# Ground_Station_Board.net
KiCad netlist of a schematic drawn in EAGLE
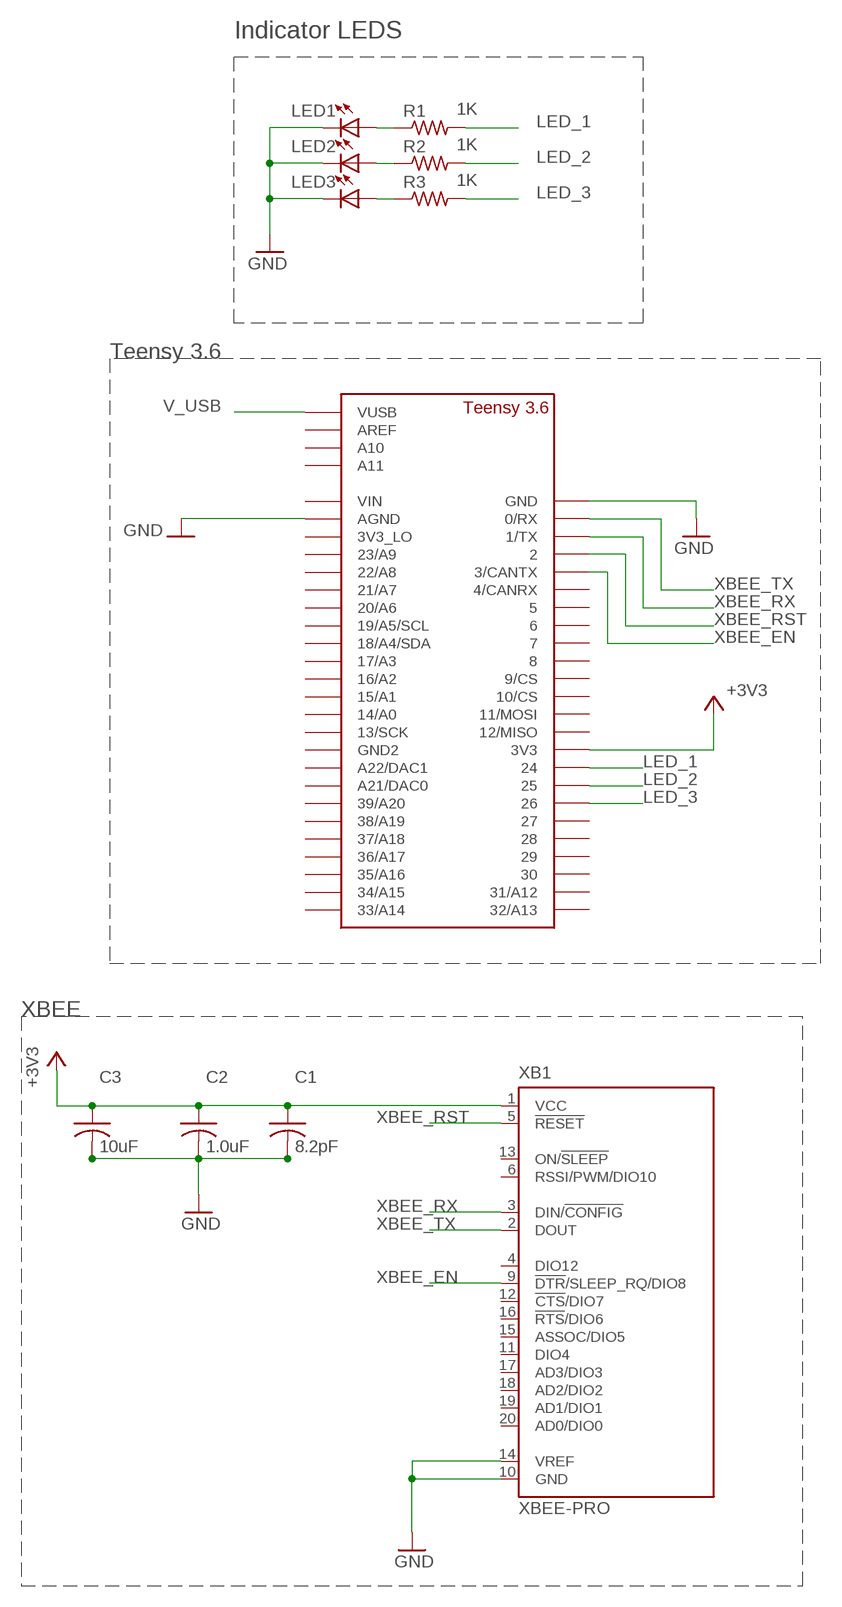
[diagram p0: schematic, sheet 1]

(export (version "E")
  (design (tool "Eeschema 10.0.6"))
  (components
    (comp (ref "C1")
      (value "8.2pF")
      (footprint "eagle-import:C025-024X044")
      (libsource (lib "eagle-import") (part "C-US025-024X044"))
    )
    (comp (ref "C2")
      (value "1.0uF")
      (footprint "eagle-import:C025-024X044")
      (libsource (lib "eagle-import") (part "C-US025-024X044"))
    )
    (comp (ref "C3")
      (value "10uF")
      (footprint "eagle-import:C025-024X044")
      (libsource (lib "eagle-import") (part "C-US025-024X044"))
    )
    (comp (ref "LED1")
      (value "LED5MM")
      (footprint "eagle-import:LED5MM")
      (libsource (lib "eagle-import") (part "LED5MM"))
    )
    (comp (ref "LED2")
      (value "LED5MM")
      (footprint "eagle-import:LED5MM")
      (libsource (lib "eagle-import") (part "LED5MM"))
    )
    (comp (ref "LED3")
      (value "LED5MM")
      (footprint "eagle-import:LED5MM")
      (libsource (lib "eagle-import") (part "LED5MM"))
    )
    (comp (ref "R1")
      (value "1K")
      (footprint "eagle-import:0207_7")
      (libsource (lib "eagle-import") (part "R-US_0207/7"))
    )
    (comp (ref "R2")
      (value "1K")
      (footprint "eagle-import:0207_7")
      (libsource (lib "eagle-import") (part "R-US_0207/7"))
    )
    (comp (ref "R3")
      (value "1K")
      (footprint "eagle-import:0207_7")
      (libsource (lib "eagle-import") (part "R-US_0207/7"))
    )
    (comp (ref "U$2")
      (value "TEENSY_3.5/3.6_BASIC")
      (footprint "eagle-import:TEENSY_3.5_3.6_BASIC")
      (libsource (lib "eagle-import") (part "TEENSY_3.5/3.6_BASIC"))
    )
    (comp (ref "XB1")
      (value "XBEE-PRO")
      (footprint "eagle-import:XBEE-PRO")
      (fields (field (name "MPN") "XBP24-AWI-001"))
      (libsource (lib "eagle-import") (part "XBEE-PRO"))
    )
  )
  (nets
    (net (code "1") (name "+3V3") (class "Default")
      (node (ref "C1") (pin "1") (pinfunction "1_1") (pintype "passive"))
      (node (ref "C2") (pin "1") (pinfunction "1_1") (pintype "passive"))
      (node (ref "C3") (pin "1") (pinfunction "1_1") (pintype "passive"))
      (node (ref "U$2") (pin "3V3") (pinfunction "3V3_3V3") (pintype "bidirectional"))
      (node (ref "XB1") (pin "1") (pinfunction "VCC_1") (pintype "power_in"))
    )
    (net (code "2") (name "/LED_1") (class "Default")
      (node (ref "R1") (pin "2") (pinfunction "2_2") (pintype "passive"))
      (node (ref "U$2") (pin "24") (pinfunction "24_24") (pintype "bidirectional"))
    )
    (net (code "3") (name "/LED_2") (class "Default")
      (node (ref "R2") (pin "2") (pinfunction "2_2") (pintype "passive"))
      (node (ref "U$2") (pin "25") (pinfunction "25_25") (pintype "bidirectional"))
    )
    (net (code "4") (name "/LED_3") (class "Default")
      (node (ref "R3") (pin "2") (pinfunction "2_2") (pintype "passive"))
      (node (ref "U$2") (pin "26") (pinfunction "26_26") (pintype "bidirectional"))
    )
    (net (code "5") (name "/V_USB") (class "Default")
      (node (ref "U$2") (pin "VUSB") (pinfunction "VUSB_VUSB") (pintype "bidirectional"))
    )
    (net (code "6") (name "/XBEE_EN") (class "Default")
      (node (ref "U$2") (pin "3/CANTX") (pinfunction "3/CANTX_3/CANTX") (pintype "bidirectional"))
      (node (ref "XB1") (pin "9") (pinfunction "~{DTR}/SLEEP_RQ/DIO8_9") (pintype "bidirectional"))
    )
    (net (code "7") (name "/XBEE_RST") (class "Default")
      (node (ref "U$2") (pin "2") (pinfunction "2_2") (pintype "bidirectional"))
      (node (ref "XB1") (pin "5") (pinfunction "~{RESET}_5") (pintype "input"))
    )
    (net (code "8") (name "/XBEE_RX") (class "Default")
      (node (ref "U$2") (pin "1/TX") (pinfunction "1/TX_1/TX") (pintype "bidirectional"))
      (node (ref "XB1") (pin "3") (pinfunction "DIN/~{CONFIG}_3") (pintype "input"))
    )
    (net (code "9") (name "/XBEE_TX") (class "Default")
      (node (ref "U$2") (pin "0/RX") (pinfunction "0/RX_0/RX") (pintype "bidirectional"))
      (node (ref "XB1") (pin "2") (pinfunction "DOUT_2") (pintype "output"))
    )
    (net (code "10") (name "GND") (class "Default")
      (node (ref "C1") (pin "2") (pinfunction "2_2") (pintype "passive"))
      (node (ref "C2") (pin "2") (pinfunction "2_2") (pintype "passive"))
      (node (ref "C3") (pin "2") (pinfunction "2_2") (pintype "passive"))
      (node (ref "LED1") (pin "K") (pinfunction "C_K") (pintype "passive"))
      (node (ref "LED2") (pin "K") (pinfunction "C_K") (pintype "passive"))
      (node (ref "LED3") (pin "K") (pinfunction "C_K") (pintype "passive"))
      (node (ref "U$2") (pin "AGND") (pinfunction "AGND_AGND") (pintype "bidirectional"))
      (node (ref "U$2") (pin "GND") (pinfunction "GND_GND") (pintype "bidirectional"))
      (node (ref "XB1") (pin "10") (pinfunction "GND_10") (pintype "power_in"))
      (node (ref "XB1") (pin "14") (pinfunction "VREF_14") (pintype "input"))
    )
    (net (code "11") (name "Net-(LED1-PadA)") (class "Default")
      (node (ref "LED1") (pin "A") (pinfunction "A_A") (pintype "passive"))
      (node (ref "R1") (pin "1") (pinfunction "1_1") (pintype "passive"))
    )
    (net (code "12") (name "Net-(LED2-PadA)") (class "Default")
      (node (ref "LED2") (pin "A") (pinfunction "A_A") (pintype "passive"))
      (node (ref "R2") (pin "1") (pinfunction "1_1") (pintype "passive"))
    )
    (net (code "13") (name "Net-(LED3-PadA)") (class "Default")
      (node (ref "LED3") (pin "A") (pinfunction "A_A") (pintype "passive"))
      (node (ref "R3") (pin "1") (pinfunction "1_1") (pintype "passive"))
    )
    (net (code "14") (name "unconnected-(U$2-A21{slash}DAC0-Pad21{slash}DAC0)") (class "Default")
      (node (ref "U$2") (pin "21/DAC0") (pinfunction "A21/DAC0_21/DAC0") (pintype "bidirectional"))
    )
    (net (code "15") (name "unconnected-(U$2-Pad3V3_LO)") (class "Default")
      (node (ref "U$2") (pin "3V3_LO") (pinfunction "3V3_LO_3V3_LO") (pintype "bidirectional"))
    )
    (net (code "16") (name "unconnected-(U$2-Pad4{slash}CANRX)") (class "Default")
      (node (ref "U$2") (pin "4/CANRX") (pinfunction "4/CANRX_4/CANRX") (pintype "bidirectional"))
    )
    (net (code "17") (name "unconnected-(U$2-Pad5)") (class "Default")
      (node (ref "U$2") (pin "5") (pinfunction "5_5") (pintype "bidirectional"))
    )
    (net (code "18") (name "unconnected-(U$2-Pad6)") (class "Default")
      (node (ref "U$2") (pin "6") (pinfunction "6_6") (pintype "bidirectional"))
    )
    (net (code "19") (name "unconnected-(U$2-Pad7)") (class "Default")
      (node (ref "U$2") (pin "7") (pinfunction "7_7") (pintype "bidirectional"))
    )
    (net (code "20") (name "unconnected-(U$2-Pad8)") (class "Default")
      (node (ref "U$2") (pin "8") (pinfunction "8_8") (pintype "bidirectional"))
    )
    (net (code "21") (name "unconnected-(U$2-Pad9{slash}CS)") (class "Default")
      (node (ref "U$2") (pin "9/CS") (pinfunction "9/CS_9/CS") (pintype "bidirectional"))
    )
    (net (code "22") (name "unconnected-(U$2-Pad10{slash}CS)") (class "Default")
      (node (ref "U$2") (pin "10/CS") (pinfunction "10/CS_10/CS") (pintype "bidirectional"))
    )
    (net (code "23") (name "unconnected-(U$2-Pad11{slash}MOSI)") (class "Default")
      (node (ref "U$2") (pin "11/MOSI") (pinfunction "11/MOSI_11/MOSI") (pintype "bidirectional"))
    )
    (net (code "24") (name "unconnected-(U$2-Pad12{slash}MISO)") (class "Default")
      (node (ref "U$2") (pin "12/MISO") (pinfunction "12/MISO_12/MISO") (pintype "bidirectional"))
    )
    (net (code "25") (name "unconnected-(U$2-Pad13{slash}SCK)") (class "Default")
      (node (ref "U$2") (pin "13/SCK") (pinfunction "13/SCK_13/SCK") (pintype "bidirectional"))
    )
    (net (code "26") (name "unconnected-(U$2-Pad14{slash}A0)") (class "Default")
      (node (ref "U$2") (pin "14/A0") (pinfunction "14/A0_14/A0") (pintype "bidirectional"))
    )
    (net (code "27") (name "unconnected-(U$2-Pad15{slash}A1)") (class "Default")
      (node (ref "U$2") (pin "15/A1") (pinfunction "15/A1_15/A1") (pintype "bidirectional"))
    )
    (net (code "28") (name "unconnected-(U$2-Pad16{slash}A2)") (class "Default")
      (node (ref "U$2") (pin "16/A2") (pinfunction "16/A2_16/A2") (pintype "bidirectional"))
    )
    (net (code "29") (name "unconnected-(U$2-Pad17{slash}A3)") (class "Default")
      (node (ref "U$2") (pin "17/A3") (pinfunction "17/A3_17/A3") (pintype "bidirectional"))
    )
    (net (code "30") (name "unconnected-(U$2-Pad18{slash}A4{slash}SDA)") (class "Default")
      (node (ref "U$2") (pin "18/A4/SDA") (pinfunction "18/A4/SDA_18/A4/SDA") (pintype "bidirectional"))
    )
    (net (code "31") (name "unconnected-(U$2-Pad19{slash}A5{slash}SCL)") (class "Default")
      (node (ref "U$2") (pin "19/A5/SCL") (pinfunction "19/A5/SCL_19/A5/SCL") (pintype "bidirectional"))
    )
    (net (code "32") (name "unconnected-(U$2-Pad20{slash}A6)") (class "Default")
      (node (ref "U$2") (pin "20/A6") (pinfunction "20/A6_20/A6") (pintype "bidirectional"))
    )
    (net (code "33") (name "unconnected-(U$2-Pad21{slash}A7)") (class "Default")
      (node (ref "U$2") (pin "21/A7") (pinfunction "21/A7_21/A7") (pintype "bidirectional"))
    )
    (net (code "34") (name "unconnected-(U$2-Pad22{slash}A8)") (class "Default")
      (node (ref "U$2") (pin "22/A8") (pinfunction "22/A8_22/A8") (pintype "bidirectional"))
    )
    (net (code "35") (name "unconnected-(U$2-Pad23{slash}A9)") (class "Default")
      (node (ref "U$2") (pin "23/A9") (pinfunction "23/A9_23/A9") (pintype "bidirectional"))
    )
    (net (code "36") (name "unconnected-(U$2-Pad27)") (class "Default")
      (node (ref "U$2") (pin "27") (pinfunction "27_27") (pintype "bidirectional"))
    )
    (net (code "37") (name "unconnected-(U$2-Pad28)") (class "Default")
      (node (ref "U$2") (pin "28") (pinfunction "28_28") (pintype "bidirectional"))
    )
    (net (code "38") (name "unconnected-(U$2-Pad29)") (class "Default")
      (node (ref "U$2") (pin "29") (pinfunction "29_29") (pintype "bidirectional"))
    )
    (net (code "39") (name "unconnected-(U$2-Pad30)") (class "Default")
      (node (ref "U$2") (pin "30") (pinfunction "30_30") (pintype "bidirectional"))
    )
    (net (code "40") (name "unconnected-(U$2-Pad31{slash}A12)") (class "Default")
      (node (ref "U$2") (pin "31/A12") (pinfunction "31/A12_31/A12") (pintype "bidirectional"))
    )
    (net (code "41") (name "unconnected-(U$2-Pad32{slash}A13)") (class "Default")
      (node (ref "U$2") (pin "32/A13") (pinfunction "32/A13_32/A13") (pintype "bidirectional"))
    )
    (net (code "42") (name "unconnected-(U$2-Pad33{slash}A14)") (class "Default")
      (node (ref "U$2") (pin "33/A14") (pinfunction "33/A14_33/A14") (pintype "bidirectional"))
    )
    (net (code "43") (name "unconnected-(U$2-Pad34{slash}A15)") (class "Default")
      (node (ref "U$2") (pin "34/A15") (pinfunction "34/A15_34/A15") (pintype "bidirectional"))
    )
    (net (code "44") (name "unconnected-(U$2-Pad35{slash}A16)") (class "Default")
      (node (ref "U$2") (pin "35/A16") (pinfunction "35/A16_35/A16") (pintype "bidirectional"))
    )
    (net (code "45") (name "unconnected-(U$2-Pad36{slash}A17)") (class "Default")
      (node (ref "U$2") (pin "36/A17") (pinfunction "36/A17_36/A17") (pintype "bidirectional"))
    )
    (net (code "46") (name "unconnected-(U$2-Pad37{slash}A18)") (class "Default")
      (node (ref "U$2") (pin "37/A18") (pinfunction "37/A18_37/A18") (pintype "bidirectional"))
    )
    (net (code "47") (name "unconnected-(U$2-Pad38{slash}A19)") (class "Default")
      (node (ref "U$2") (pin "38/A19") (pinfunction "38/A19_38/A19") (pintype "bidirectional"))
    )
    (net (code "48") (name "unconnected-(U$2-Pad39{slash}A20)") (class "Default")
      (node (ref "U$2") (pin "39/A20") (pinfunction "39/A20_39/A20") (pintype "bidirectional"))
    )
    (net (code "49") (name "unconnected-(U$2-PadA10)") (class "Default")
      (node (ref "U$2") (pin "A10") (pinfunction "A10_A10") (pintype "bidirectional"))
    )
    (net (code "50") (name "unconnected-(U$2-PadA11)") (class "Default")
      (node (ref "U$2") (pin "A11") (pinfunction "A11_A11") (pintype "bidirectional"))
    )
    (net (code "51") (name "unconnected-(U$2-PadA22{slash}DAC1)") (class "Default")
      (node (ref "U$2") (pin "A22/DAC1") (pinfunction "A22/DAC1_A22/DAC1") (pintype "bidirectional"))
    )
    (net (code "52") (name "unconnected-(U$2-PadAREF)") (class "Default")
      (node (ref "U$2") (pin "AREF") (pinfunction "AREF_AREF") (pintype "bidirectional"))
    )
    (net (code "53") (name "unconnected-(U$2-PadGND2)") (class "Default")
      (node (ref "U$2") (pin "GND2") (pinfunction "GND2_GND2") (pintype "bidirectional"))
    )
    (net (code "54") (name "unconnected-(U$2-PadVIN)") (class "Default")
      (node (ref "U$2") (pin "VIN") (pinfunction "VIN_VIN") (pintype "bidirectional"))
    )
    (net (code "55") (name "unconnected-(XB1-AD0{slash}DIO0-Pad20)") (class "Default")
      (node (ref "XB1") (pin "20") (pinfunction "AD0/DIO0_20") (pintype "bidirectional"))
    )
    (net (code "56") (name "unconnected-(XB1-AD1{slash}DIO1-Pad19)") (class "Default")
      (node (ref "XB1") (pin "19") (pinfunction "AD1/DIO1_19") (pintype "bidirectional"))
    )
    (net (code "57") (name "unconnected-(XB1-AD2{slash}DIO2-Pad18)") (class "Default")
      (node (ref "XB1") (pin "18") (pinfunction "AD2/DIO2_18") (pintype "bidirectional"))
    )
    (net (code "58") (name "unconnected-(XB1-AD3{slash}DIO3-Pad17)") (class "Default")
      (node (ref "XB1") (pin "17") (pinfunction "AD3/DIO3_17") (pintype "bidirectional"))
    )
    (net (code "59") (name "unconnected-(XB1-ASSOC{slash}DIO5-Pad15)") (class "Default")
      (node (ref "XB1") (pin "15") (pinfunction "ASSOC/DIO5_15") (pintype "bidirectional"))
    )
    (net (code "60") (name "unconnected-(XB1-DIO4-Pad11)") (class "Default")
      (node (ref "XB1") (pin "11") (pinfunction "DIO4_11") (pintype "bidirectional"))
    )
    (net (code "61") (name "unconnected-(XB1-DIO12-Pad4)") (class "Default")
      (node (ref "XB1") (pin "4") (pinfunction "DIO12_4") (pintype "bidirectional"))
    )
    (net (code "62") (name "unconnected-(XB1-ON{slash}~{SLEEP}-Pad13)") (class "Default")
      (node (ref "XB1") (pin "13") (pinfunction "ON/~{SLEEP}_13") (pintype "output"))
    )
    (net (code "63") (name "unconnected-(XB1-RSSI{slash}PWM{slash}DIO10-Pad6)") (class "Default")
      (node (ref "XB1") (pin "6") (pinfunction "RSSI/PWM/DIO10_6") (pintype "output"))
    )
    (net (code "64") (name "unconnected-(XB1-~{CTS}{slash}DIO7-Pad12)") (class "Default")
      (node (ref "XB1") (pin "12") (pinfunction "~{CTS}/DIO7_12") (pintype "bidirectional"))
    )
    (net (code "65") (name "unconnected-(XB1-~{RTS}{slash}DIO6-Pad16)") (class "Default")
      (node (ref "XB1") (pin "16") (pinfunction "~{RTS}/DIO6_16") (pintype "bidirectional"))
    )
  )
)
